# TSOP_jr3.net
KiCad netlist of a schematic drawn in EAGLE
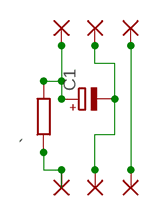
[diagram p0: schematic, sheet 1]

(export (version "E")
  (design (tool "Eeschema 10.0.6"))
  (components
    (comp (ref "\"")
      (value "1,6/0,9")
      (footprint "eagle-import:1,6_0,9")
      (libsource (lib "eagle-import") (part "1,6/0,9"))
    )
    (comp (ref "\"\"")
      (value "1,6/0,9")
      (footprint "eagle-import:1,6_0,9")
      (libsource (lib "eagle-import") (part "1,6/0,9"))
    )
    (comp (ref "\"\"\"")
      (value "1,6/0,9")
      (footprint "eagle-import:1,6_0,9")
      (libsource (lib "eagle-import") (part "1,6/0,9"))
    )
    (comp (ref "....")
      (value "1,6/0,9")
      (footprint "eagle-import:1,6_0,9")
      (libsource (lib "eagle-import") (part "1,6/0,9"))
    )
    (comp (ref ".....")
      (value "1,6/0,9")
      (footprint "eagle-import:1,6_0,9")
      (libsource (lib "eagle-import") (part "1,6/0,9"))
    )
    (comp (ref "......")
      (value "1,6/0,9")
      (footprint "eagle-import:1,6_0,9")
      (libsource (lib "eagle-import") (part "1,6/0,9"))
    )
    (comp (ref "C1")
      (value "CPOL-EUE1.8-4")
      (footprint "eagle-import:E1,8-4")
      (libsource (lib "eagle-import") (part "CPOL-EUE1.8-4"))
    )
    (comp (ref "`")
      (value "R-EU_0204/5")
      (footprint "eagle-import:0204_5")
      (libsource (lib "eagle-import") (part "R-EU_0204/5"))
    )
  )
  (nets
    (net (code "1") (name "Net-(\"\"\"-P)") (class "Default")
      (node (ref "\"\"\"") (pin "1") (pinfunction "P_1") (pintype "passive"))
      (node (ref "C1") (pin "+") (pinfunction "+_+") (pintype "passive"))
      (node (ref "`") (pin "2") (pinfunction "2_2") (pintype "passive"))
    )
    (net (code "2") (name "Net-(\"\"-P)") (class "Default")
      (node (ref "\"\"") (pin "1") (pinfunction "P_1") (pintype "passive"))
      (node (ref ".....") (pin "1") (pinfunction "P_1") (pintype "passive"))
      (node (ref "C1") (pin "-") (pinfunction "-_-") (pintype "passive"))
    )
    (net (code "3") (name "Net-(\"-P)") (class "Default")
      (node (ref "\"") (pin "1") (pinfunction "P_1") (pintype "passive"))
      (node (ref "......") (pin "1") (pinfunction "P_1") (pintype "passive"))
    )
    (net (code "4") (name "Net-(....-P)") (class "Default")
      (node (ref "....") (pin "1") (pinfunction "P_1") (pintype "passive"))
      (node (ref "`") (pin "1") (pinfunction "1_1") (pintype "passive"))
    )
  )
)
